# Jeep_BT_Switcher.net
KiCad netlist of a schematic drawn in EAGLE
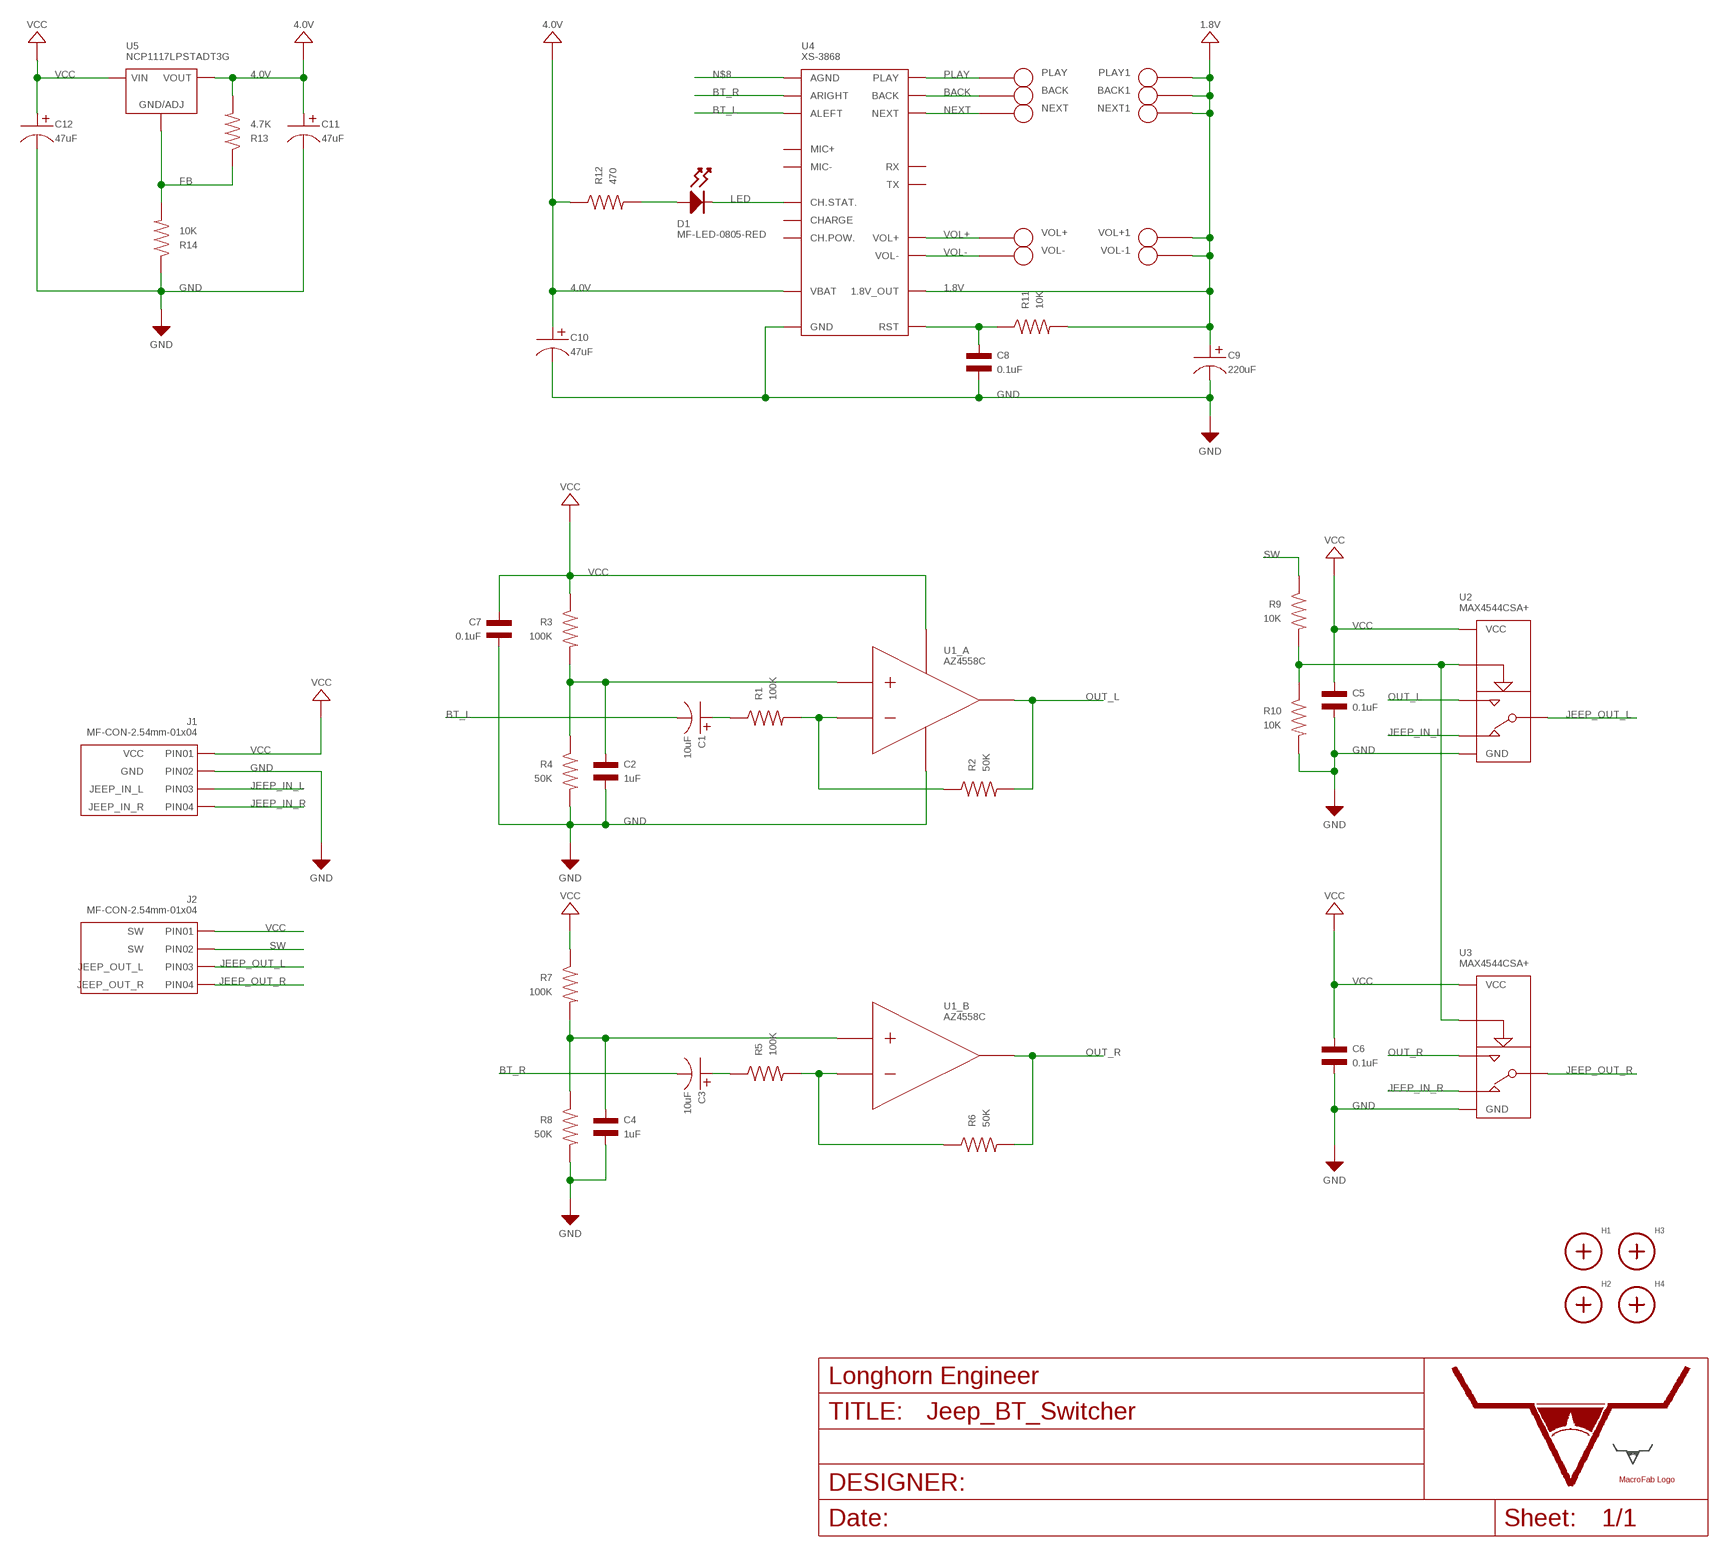
[diagram p0: schematic, sheet 1]

(export (version "E")
  (design (tool "Eeschema 10.0.6"))
  (components
    (comp (ref "BACK")
      (value "TEST_POINT_SINGLE_ROUND_1MM")
      (footprint "eagle-import:ROUND_TP")
      (libsource (lib "eagle-import") (part "TEST_POINT_SINGLE_ROUND_1MM"))
    )
    (comp (ref "BACK1")
      (value "TEST_POINT_SINGLE_ROUND_1MM")
      (footprint "eagle-import:ROUND_TP")
      (libsource (lib "eagle-import") (part "TEST_POINT_SINGLE_ROUND_1MM"))
    )
    (comp (ref "C1")
      (value "10uF")
      (footprint "eagle-import:CP4MM")
      (libsource (lib "eagle-import") (part "CAPACITOR_P_4MM"))
    )
    (comp (ref "C2")
      (value "1uF")
      (footprint "eagle-import:C0805")
      (libsource (lib "eagle-import") (part "CAPACITOR_NP_0805"))
    )
    (comp (ref "C3")
      (value "10uF")
      (footprint "eagle-import:CP4MM")
      (libsource (lib "eagle-import") (part "CAPACITOR_P_4MM"))
    )
    (comp (ref "C4")
      (value "1uF")
      (footprint "eagle-import:C0805")
      (libsource (lib "eagle-import") (part "CAPACITOR_NP_0805"))
    )
    (comp (ref "C5")
      (value "0.1uF")
      (footprint "eagle-import:C0805")
      (libsource (lib "eagle-import") (part "CAPACITOR_NP_0805"))
    )
    (comp (ref "C6")
      (value "0.1uF")
      (footprint "eagle-import:C0805")
      (libsource (lib "eagle-import") (part "CAPACITOR_NP_0805"))
    )
    (comp (ref "C7")
      (value "0.1uF")
      (footprint "eagle-import:C0805")
      (libsource (lib "eagle-import") (part "CAPACITOR_NP_0805"))
    )
    (comp (ref "C8")
      (value "0.1uF")
      (footprint "eagle-import:C0805")
      (libsource (lib "eagle-import") (part "CAPACITOR_NP_0805"))
    )
    (comp (ref "C9")
      (value "220uF")
      (footprint "eagle-import:CP10MM")
      (libsource (lib "eagle-import") (part "CAPACITOR_P_10MM"))
    )
    (comp (ref "C10")
      (value "47uF")
      (footprint "eagle-import:CP6.3MM")
      (libsource (lib "eagle-import") (part "CAPACITOR_P_6.3MM"))
    )
    (comp (ref "C11")
      (value "47uF")
      (footprint "eagle-import:CP6.3MM")
      (libsource (lib "eagle-import") (part "CAPACITOR_P_6.3MM"))
    )
    (comp (ref "C12")
      (value "47uF")
      (footprint "eagle-import:CP6.3MM")
      (libsource (lib "eagle-import") (part "CAPACITOR_P_6.3MM"))
    )
    (comp (ref "D1")
      (value "MF-LED-0805-RED")
      (footprint "eagle-import:LED0805")
      (fields (field (name "HOUSEPART") "YES"))
      (libsource (lib "eagle-import") (part "LED_SINGLE-0805-RED"))
    )
    (comp (ref "H1")
      (value "MOUNT_HOLE150MIL")
      (footprint "eagle-import:MOUNT_HOLE_150MIL")
      (libsource (lib "eagle-import") (part "MOUNT_HOLE150MIL"))
    )
    (comp (ref "H2")
      (value "MOUNT_HOLE150MIL")
      (footprint "eagle-import:MOUNT_HOLE_150MIL")
      (libsource (lib "eagle-import") (part "MOUNT_HOLE150MIL"))
    )
    (comp (ref "H3")
      (value "MOUNT_HOLE150MIL")
      (footprint "eagle-import:MOUNT_HOLE_150MIL")
      (libsource (lib "eagle-import") (part "MOUNT_HOLE150MIL"))
    )
    (comp (ref "H4")
      (value "MOUNT_HOLE150MIL")
      (footprint "eagle-import:MOUNT_HOLE_150MIL")
      (libsource (lib "eagle-import") (part "MOUNT_HOLE150MIL"))
    )
    (comp (ref "J1")
      (value "MF-CON-2.54mm-01x04")
      (footprint "eagle-import:PTH_2.54MM_01X04")
      (fields
        (field (name "HOUSEPART") "YES")
        (field (name "LABEL01") "VCC")
        (field (name "LABEL02") "GND")
        (field (name "LABEL03") "JEEP_IN_L")
        (field (name "LABEL04") "JEEP_IN_R")
      )
      (libsource (lib "eagle-import") (part "CON_01X04_PTH_2.54MM"))
    )
    (comp (ref "J2")
      (value "MF-CON-2.54mm-01x04")
      (footprint "eagle-import:PTH_2.54MM_01X04")
      (fields
        (field (name "HOUSEPART") "YES")
        (field (name "LABEL01") "SW")
        (field (name "LABEL02") "SW")
        (field (name "LABEL03") "JEEP_OUT_L")
        (field (name "LABEL04") "JEEP_OUT_R")
      )
      (libsource (lib "eagle-import") (part "CON_01X04_PTH_2.54MM"))
    )
    (comp (ref "NEXT")
      (value "TEST_POINT_SINGLE_ROUND_1MM")
      (footprint "eagle-import:ROUND_TP")
      (libsource (lib "eagle-import") (part "TEST_POINT_SINGLE_ROUND_1MM"))
    )
    (comp (ref "NEXT1")
      (value "TEST_POINT_SINGLE_ROUND_1MM")
      (footprint "eagle-import:ROUND_TP")
      (libsource (lib "eagle-import") (part "TEST_POINT_SINGLE_ROUND_1MM"))
    )
    (comp (ref "PLAY")
      (value "TEST_POINT_SINGLE_ROUND_1MM")
      (footprint "eagle-import:ROUND_TP")
      (libsource (lib "eagle-import") (part "TEST_POINT_SINGLE_ROUND_1MM"))
    )
    (comp (ref "PLAY1")
      (value "TEST_POINT_SINGLE_ROUND_1MM")
      (footprint "eagle-import:ROUND_TP")
      (libsource (lib "eagle-import") (part "TEST_POINT_SINGLE_ROUND_1MM"))
    )
    (comp (ref "R1")
      (value "100K")
      (footprint "eagle-import:R0805")
      (libsource (lib "eagle-import") (part "RESISTOR_0805"))
    )
    (comp (ref "R2")
      (value "50K")
      (footprint "eagle-import:R0805")
      (libsource (lib "eagle-import") (part "RESISTOR_0805"))
    )
    (comp (ref "R3")
      (value "100K")
      (footprint "eagle-import:R0805")
      (libsource (lib "eagle-import") (part "RESISTOR_0805"))
    )
    (comp (ref "R4")
      (value "50K")
      (footprint "eagle-import:R0805")
      (libsource (lib "eagle-import") (part "RESISTOR_0805"))
    )
    (comp (ref "R5")
      (value "100K")
      (footprint "eagle-import:R0805")
      (libsource (lib "eagle-import") (part "RESISTOR_0805"))
    )
    (comp (ref "R6")
      (value "50K")
      (footprint "eagle-import:R0805")
      (libsource (lib "eagle-import") (part "RESISTOR_0805"))
    )
    (comp (ref "R7")
      (value "100K")
      (footprint "eagle-import:R0805")
      (libsource (lib "eagle-import") (part "RESISTOR_0805"))
    )
    (comp (ref "R8")
      (value "50K")
      (footprint "eagle-import:R0805")
      (libsource (lib "eagle-import") (part "RESISTOR_0805"))
    )
    (comp (ref "R9")
      (value "10K")
      (footprint "eagle-import:R0805")
      (libsource (lib "eagle-import") (part "RESISTOR_0805"))
    )
    (comp (ref "R10")
      (value "10K")
      (footprint "eagle-import:R0805")
      (libsource (lib "eagle-import") (part "RESISTOR_0805"))
    )
    (comp (ref "R11")
      (value "10K")
      (footprint "eagle-import:R0805")
      (libsource (lib "eagle-import") (part "RESISTOR_0805"))
    )
    (comp (ref "R12")
      (value "470")
      (footprint "eagle-import:R0805")
      (libsource (lib "eagle-import") (part "RESISTOR_0805"))
    )
    (comp (ref "R13")
      (value "4.7K")
      (footprint "eagle-import:R0805")
      (libsource (lib "eagle-import") (part "RESISTOR_0805"))
    )
    (comp (ref "R14")
      (value "10K")
      (footprint "eagle-import:R0805")
      (libsource (lib "eagle-import") (part "RESISTOR_0805"))
    )
    (comp (ref "U$11")
      (value "LHE_FRAME")
      (footprint "eagle-import:LHE_FRAME")
      (fields (field (name "DNAME") "Parker Dillmann") (field (name "REVNUM") "REV: 3"))
      (libsource (lib "eagle-import") (part "LHE_FRAME"))
    )
    (comp (ref "U$12")
      (value "MF_LOGOLOGO_SMALL")
      (footprint "eagle-import:MF_LOGO_SMALL")
      (libsource (lib "eagle-import") (part "MF_LOGOLOGO_SMALL"))
    )
    (comp (ref "U$13")
      (value "LHE_LOGOLHE_LOGO")
      (footprint "eagle-import:LHE_LOGO")
      (libsource (lib "eagle-import") (part "LHE_LOGOLHE_LOGO"))
    )
    (comp (ref "U1")
      (value "AZ4558C")
      (footprint "eagle-import:AZ4558C_SOIC-8")
      (libsource (lib "eagle-import") (part "AZ4558C"))
    )
    (comp (ref "U2")
      (value "MAX4544CSA+")
      (footprint "eagle-import:AZ4558C_SOIC-8")
      (libsource (lib "eagle-import") (part "MAX4544"))
    )
    (comp (ref "U3")
      (value "MAX4544CSA+")
      (footprint "eagle-import:AZ4558C_SOIC-8")
      (libsource (lib "eagle-import") (part "MAX4544"))
    )
    (comp (ref "U4")
      (value "XS-3868")
      (footprint "eagle-import:XS3868")
      (libsource (lib "eagle-import") (part "XS3868"))
    )
    (comp (ref "U5")
      (value "NCP1117LPSTADT3G")
      (footprint "eagle-import:SOT-223-3")
      (fields (field (name "HOUSEPART") "NO"))
      (libsource (lib "eagle-import") (part "NCP1117LPSTADT3G"))
    )
    (comp (ref "VOL+")
      (value "TEST_POINT_SINGLE_ROUND_1MM")
      (footprint "eagle-import:ROUND_TP")
      (libsource (lib "eagle-import") (part "TEST_POINT_SINGLE_ROUND_1MM"))
    )
    (comp (ref "VOL+1")
      (value "TEST_POINT_SINGLE_ROUND_1MM")
      (footprint "eagle-import:ROUND_TP")
      (libsource (lib "eagle-import") (part "TEST_POINT_SINGLE_ROUND_1MM"))
    )
    (comp (ref "VOL-")
      (value "TEST_POINT_SINGLE_ROUND_1MM")
      (footprint "eagle-import:ROUND_TP")
      (libsource (lib "eagle-import") (part "TEST_POINT_SINGLE_ROUND_1MM"))
    )
    (comp (ref "VOL-1")
      (value "TEST_POINT_SINGLE_ROUND_1MM")
      (footprint "eagle-import:ROUND_TP")
      (libsource (lib "eagle-import") (part "TEST_POINT_SINGLE_ROUND_1MM"))
    )
  )
  (nets
    (net (code "1") (name "/BACK") (class "Default")
      (node (ref "BACK") (pin "P$1") (pinfunction "P$1_P$1") (pintype "bidirectional"))
      (node (ref "U4") (pin "BACK") (pinfunction "BACK_BACK") (pintype "bidirectional"))
    )
    (net (code "2") (name "/BT_L") (class "Default")
      (node (ref "C1") (pin "P$2") (pinfunction "P$2_P$2") (pintype "passive"))
      (node (ref "U4") (pin "ALEFT") (pinfunction "ALEFT_ALEFT") (pintype "bidirectional"))
    )
    (net (code "3") (name "/BT_R") (class "Default")
      (node (ref "C3") (pin "P$2") (pinfunction "P$2_P$2") (pintype "passive"))
      (node (ref "U4") (pin "ARIGHT") (pinfunction "ARIGHT_ARIGHT") (pintype "bidirectional"))
    )
    (net (code "4") (name "/FB") (class "Default")
      (node (ref "R13") (pin "P$1") (pinfunction "P$1_P$1") (pintype "passive"))
      (node (ref "R14") (pin "P$2") (pinfunction "P$2_P$2") (pintype "passive"))
      (node (ref "U5") (pin "P$2") (pinfunction "GND/ADJ_P$2") (pintype "bidirectional"))
    )
    (net (code "5") (name "/JEEP_IN_L") (class "Default")
      (node (ref "J1") (pin "P$3") (pinfunction "PIN3_P$3") (pintype "bidirectional"))
      (node (ref "U2") (pin "3") (pinfunction "NC_3") (pintype "bidirectional"))
    )
    (net (code "6") (name "/JEEP_IN_R") (class "Default")
      (node (ref "J1") (pin "P$4") (pinfunction "PIN4_P$4") (pintype "bidirectional"))
      (node (ref "U3") (pin "3") (pinfunction "NC_3") (pintype "bidirectional"))
    )
    (net (code "7") (name "/JEEP_OUT_L") (class "Default")
      (node (ref "J2") (pin "P$3") (pinfunction "PIN3_P$3") (pintype "bidirectional"))
      (node (ref "U2") (pin "2") (pinfunction "COM_2") (pintype "bidirectional"))
    )
    (net (code "8") (name "/JEEP_OUT_R") (class "Default")
      (node (ref "J2") (pin "P$4") (pinfunction "PIN4_P$4") (pintype "bidirectional"))
      (node (ref "U3") (pin "2") (pinfunction "COM_2") (pintype "bidirectional"))
    )
    (net (code "9") (name "/LED") (class "Default")
      (node (ref "D1") (pin "CATHODE") (pinfunction "CATHODE_CATHODE") (pintype "power_in"))
      (node (ref "U4") (pin "CH.STAT.") (pinfunction "CH.STAT._CH.STAT.") (pintype "bidirectional"))
    )
    (net (code "10") (name "/N$8") (class "Default")
      (node (ref "U4") (pin "AGND") (pinfunction "AGND_AGND") (pintype "bidirectional"))
    )
    (net (code "11") (name "/NEXT") (class "Default")
      (node (ref "NEXT") (pin "P$1") (pinfunction "P$1_P$1") (pintype "bidirectional"))
      (node (ref "U4") (pin "NEXT") (pinfunction "NEXT_NEXT") (pintype "bidirectional"))
    )
    (net (code "12") (name "/OUT_L") (class "Default")
      (node (ref "R2") (pin "P$2") (pinfunction "P$2_P$2") (pintype "passive"))
      (node (ref "U1") (pin "1") (pinfunction "OUTPUT_1_1") (pintype "bidirectional"))
      (node (ref "U2") (pin "1") (pinfunction "NO_1") (pintype "bidirectional"))
    )
    (net (code "13") (name "/OUT_R") (class "Default")
      (node (ref "R6") (pin "P$2") (pinfunction "P$2_P$2") (pintype "passive"))
      (node (ref "U1") (pin "7") (pinfunction "OUTPUT_2_7") (pintype "bidirectional"))
      (node (ref "U3") (pin "1") (pinfunction "NO_1") (pintype "bidirectional"))
    )
    (net (code "14") (name "/PLAY") (class "Default")
      (node (ref "PLAY") (pin "P$1") (pinfunction "P$1_P$1") (pintype "bidirectional"))
      (node (ref "U4") (pin "PLAY") (pinfunction "PLAY_PLAY") (pintype "bidirectional"))
    )
    (net (code "15") (name "/SW") (class "Default")
      (node (ref "J2") (pin "P$2") (pinfunction "PIN2_P$2") (pintype "bidirectional"))
      (node (ref "R9") (pin "P$1") (pinfunction "P$1_P$1") (pintype "passive"))
    )
    (net (code "16") (name "/VOL+") (class "Default")
      (node (ref "U4") (pin "VOL+") (pinfunction "VOL+_VOL+") (pintype "bidirectional"))
      (node (ref "VOL+") (pin "P$1") (pinfunction "P$1_P$1") (pintype "bidirectional"))
    )
    (net (code "17") (name "/VOL-") (class "Default")
      (node (ref "U4") (pin "VOL-") (pinfunction "VOL-_VOL-") (pintype "bidirectional"))
      (node (ref "VOL-") (pin "P$1") (pinfunction "P$1_P$1") (pintype "bidirectional"))
    )
    (net (code "18") (name "1.8V") (class "Default")
      (node (ref "BACK1") (pin "P$1") (pinfunction "P$1_P$1") (pintype "bidirectional"))
      (node (ref "C9") (pin "P$1") (pinfunction "P$1_P$1") (pintype "passive"))
      (node (ref "NEXT1") (pin "P$1") (pinfunction "P$1_P$1") (pintype "bidirectional"))
      (node (ref "PLAY1") (pin "P$1") (pinfunction "P$1_P$1") (pintype "bidirectional"))
      (node (ref "R11") (pin "P$2") (pinfunction "P$2_P$2") (pintype "passive"))
      (node (ref "U4") (pin "1.8V_OUT") (pinfunction "1.8V_OUT_1.8V_OUT") (pintype "bidirectional"))
      (node (ref "VOL+1") (pin "P$1") (pinfunction "P$1_P$1") (pintype "bidirectional"))
      (node (ref "VOL-1") (pin "P$1") (pinfunction "P$1_P$1") (pintype "bidirectional"))
    )
    (net (code "19") (name "4.0V") (class "Default")
      (node (ref "C10") (pin "P$1") (pinfunction "P$1_P$1") (pintype "passive"))
      (node (ref "C11") (pin "P$1") (pinfunction "P$1_P$1") (pintype "passive"))
      (node (ref "R12") (pin "P$1") (pinfunction "P$1_P$1") (pintype "passive"))
      (node (ref "R13") (pin "P$2") (pinfunction "P$2_P$2") (pintype "passive"))
      (node (ref "U4") (pin "VBAT") (pinfunction "VBAT_VBAT") (pintype "bidirectional"))
      (node (ref "U5") (pin "P$1") (pinfunction "VOUT_P$1") (pintype "bidirectional"))
      (node (ref "U5") (pin "P$3") (pinfunction "VOUT_P$3") (pintype "bidirectional"))
    )
    (net (code "20") (name "GND") (class "Default")
      (node (ref "C10") (pin "P$2") (pinfunction "P$2_P$2") (pintype "passive"))
      (node (ref "C11") (pin "P$2") (pinfunction "P$2_P$2") (pintype "passive"))
      (node (ref "C12") (pin "P$2") (pinfunction "P$2_P$2") (pintype "passive"))
      (node (ref "C2") (pin "P$2") (pinfunction "P$2_P$2") (pintype "passive"))
      (node (ref "C4") (pin "P$2") (pinfunction "P$2_P$2") (pintype "passive"))
      (node (ref "C5") (pin "P$2") (pinfunction "P$2_P$2") (pintype "passive"))
      (node (ref "C6") (pin "P$2") (pinfunction "P$2_P$2") (pintype "passive"))
      (node (ref "C7") (pin "P$2") (pinfunction "P$2_P$2") (pintype "passive"))
      (node (ref "C8") (pin "P$2") (pinfunction "P$2_P$2") (pintype "passive"))
      (node (ref "C9") (pin "P$2") (pinfunction "P$2_P$2") (pintype "passive"))
      (node (ref "J1") (pin "P$2") (pinfunction "PIN2_P$2") (pintype "bidirectional"))
      (node (ref "R10") (pin "P$2") (pinfunction "P$2_P$2") (pintype "passive"))
      (node (ref "R14") (pin "P$1") (pinfunction "P$1_P$1") (pintype "passive"))
      (node (ref "R4") (pin "P$2") (pinfunction "P$2_P$2") (pintype "passive"))
      (node (ref "R8") (pin "P$2") (pinfunction "P$2_P$2") (pintype "passive"))
      (node (ref "U1") (pin "4") (pinfunction "VEE_4") (pintype "bidirectional"))
      (node (ref "U2") (pin "4") (pinfunction "GND_4") (pintype "bidirectional"))
      (node (ref "U3") (pin "4") (pinfunction "GND_4") (pintype "bidirectional"))
      (node (ref "U4") (pin "GND") (pinfunction "GND_GND") (pintype "bidirectional"))
    )
    (net (code "21") (name "Net-(C1-PadP$1)") (class "Default")
      (node (ref "C1") (pin "P$1") (pinfunction "P$1_P$1") (pintype "passive"))
      (node (ref "R1") (pin "P$1") (pinfunction "P$1_P$1") (pintype "passive"))
    )
    (net (code "22") (name "Net-(C3-PadP$1)") (class "Default")
      (node (ref "C3") (pin "P$1") (pinfunction "P$1_P$1") (pintype "passive"))
      (node (ref "R5") (pin "P$1") (pinfunction "P$1_P$1") (pintype "passive"))
    )
    (net (code "23") (name "Net-(C8-PadP$1)") (class "Default")
      (node (ref "C8") (pin "P$1") (pinfunction "P$1_P$1") (pintype "passive"))
      (node (ref "R11") (pin "P$1") (pinfunction "P$1_P$1") (pintype "passive"))
      (node (ref "U4") (pin "RST") (pinfunction "RST_RST") (pintype "bidirectional"))
    )
    (net (code "24") (name "Net-(D1-PadANODE)") (class "Default")
      (node (ref "D1") (pin "ANODE") (pinfunction "ANODE_ANODE") (pintype "power_in"))
      (node (ref "R12") (pin "P$2") (pinfunction "P$2_P$2") (pintype "passive"))
    )
    (net (code "25") (name "Net-(U1A-INPUT_1+)") (class "Default")
      (node (ref "C2") (pin "P$1") (pinfunction "P$1_P$1") (pintype "passive"))
      (node (ref "R3") (pin "P$2") (pinfunction "P$2_P$2") (pintype "passive"))
      (node (ref "R4") (pin "P$1") (pinfunction "P$1_P$1") (pintype "passive"))
      (node (ref "U1") (pin "3") (pinfunction "INPUT_1+_3") (pintype "bidirectional"))
    )
    (net (code "26") (name "Net-(U1A-INPUT_1-)") (class "Default")
      (node (ref "R1") (pin "P$2") (pinfunction "P$2_P$2") (pintype "passive"))
      (node (ref "R2") (pin "P$1") (pinfunction "P$1_P$1") (pintype "passive"))
      (node (ref "U1") (pin "2") (pinfunction "INPUT_1-_2") (pintype "bidirectional"))
    )
    (net (code "27") (name "Net-(U1B-INPUT_2+)") (class "Default")
      (node (ref "C4") (pin "P$1") (pinfunction "P$1_P$1") (pintype "passive"))
      (node (ref "R7") (pin "P$2") (pinfunction "P$2_P$2") (pintype "passive"))
      (node (ref "R8") (pin "P$1") (pinfunction "P$1_P$1") (pintype "passive"))
      (node (ref "U1") (pin "5") (pinfunction "INPUT_2+_5") (pintype "bidirectional"))
    )
    (net (code "28") (name "Net-(U1B-INPUT_2-)") (class "Default")
      (node (ref "R5") (pin "P$2") (pinfunction "P$2_P$2") (pintype "passive"))
      (node (ref "R6") (pin "P$1") (pinfunction "P$1_P$1") (pintype "passive"))
      (node (ref "U1") (pin "6") (pinfunction "INPUT_2-_6") (pintype "bidirectional"))
    )
    (net (code "29") (name "Net-(U2-IN)") (class "Default")
      (node (ref "R10") (pin "P$1") (pinfunction "P$1_P$1") (pintype "passive"))
      (node (ref "R9") (pin "P$2") (pinfunction "P$2_P$2") (pintype "passive"))
      (node (ref "U2") (pin "7") (pinfunction "IN_7") (pintype "bidirectional"))
      (node (ref "U3") (pin "7") (pinfunction "IN_7") (pintype "bidirectional"))
    )
    (net (code "30") (name "VCC") (class "Default")
      (node (ref "C12") (pin "P$1") (pinfunction "P$1_P$1") (pintype "passive"))
      (node (ref "C5") (pin "P$1") (pinfunction "P$1_P$1") (pintype "passive"))
      (node (ref "C6") (pin "P$1") (pinfunction "P$1_P$1") (pintype "passive"))
      (node (ref "C7") (pin "P$1") (pinfunction "P$1_P$1") (pintype "passive"))
      (node (ref "J1") (pin "P$1") (pinfunction "PIN1_P$1") (pintype "bidirectional"))
      (node (ref "J2") (pin "P$1") (pinfunction "PIN1_P$1") (pintype "bidirectional"))
      (node (ref "R3") (pin "P$1") (pinfunction "P$1_P$1") (pintype "passive"))
      (node (ref "R7") (pin "P$1") (pinfunction "P$1_P$1") (pintype "passive"))
      (node (ref "U1") (pin "8") (pinfunction "VCC_8") (pintype "bidirectional"))
      (node (ref "U2") (pin "8") (pinfunction "VCC_8") (pintype "bidirectional"))
      (node (ref "U3") (pin "8") (pinfunction "VCC_8") (pintype "bidirectional"))
      (node (ref "U5") (pin "P$4") (pinfunction "VIN_P$4") (pintype "bidirectional"))
    )
    (net (code "31") (name "unconnected-(U4-PadCH.POW.)") (class "Default")
      (node (ref "U4") (pin "CH.POW.") (pinfunction "CH.POW._CH.POW.") (pintype "bidirectional"))
    )
    (net (code "32") (name "unconnected-(U4-PadCHARGE)") (class "Default")
      (node (ref "U4") (pin "CHARGE") (pinfunction "CHARGE_CHARGE") (pintype "bidirectional"))
    )
    (net (code "33") (name "unconnected-(U4-PadMIC+)") (class "Default")
      (node (ref "U4") (pin "MIC+") (pinfunction "MIC+_MIC+") (pintype "bidirectional"))
    )
    (net (code "34") (name "unconnected-(U4-PadMIC-)") (class "Default")
      (node (ref "U4") (pin "MIC-") (pinfunction "MIC-_MIC-") (pintype "bidirectional"))
    )
    (net (code "35") (name "unconnected-(U4-PadRX)") (class "Default")
      (node (ref "U4") (pin "RX") (pinfunction "RX_RX") (pintype "bidirectional"))
    )
    (net (code "36") (name "unconnected-(U4-PadTX)") (class "Default")
      (node (ref "U4") (pin "TX") (pinfunction "TX_TX") (pintype "bidirectional"))
    )
  )
)
